# 21_Peripherals.net
KiCad netlist of a schematic drawn in Altium Designer
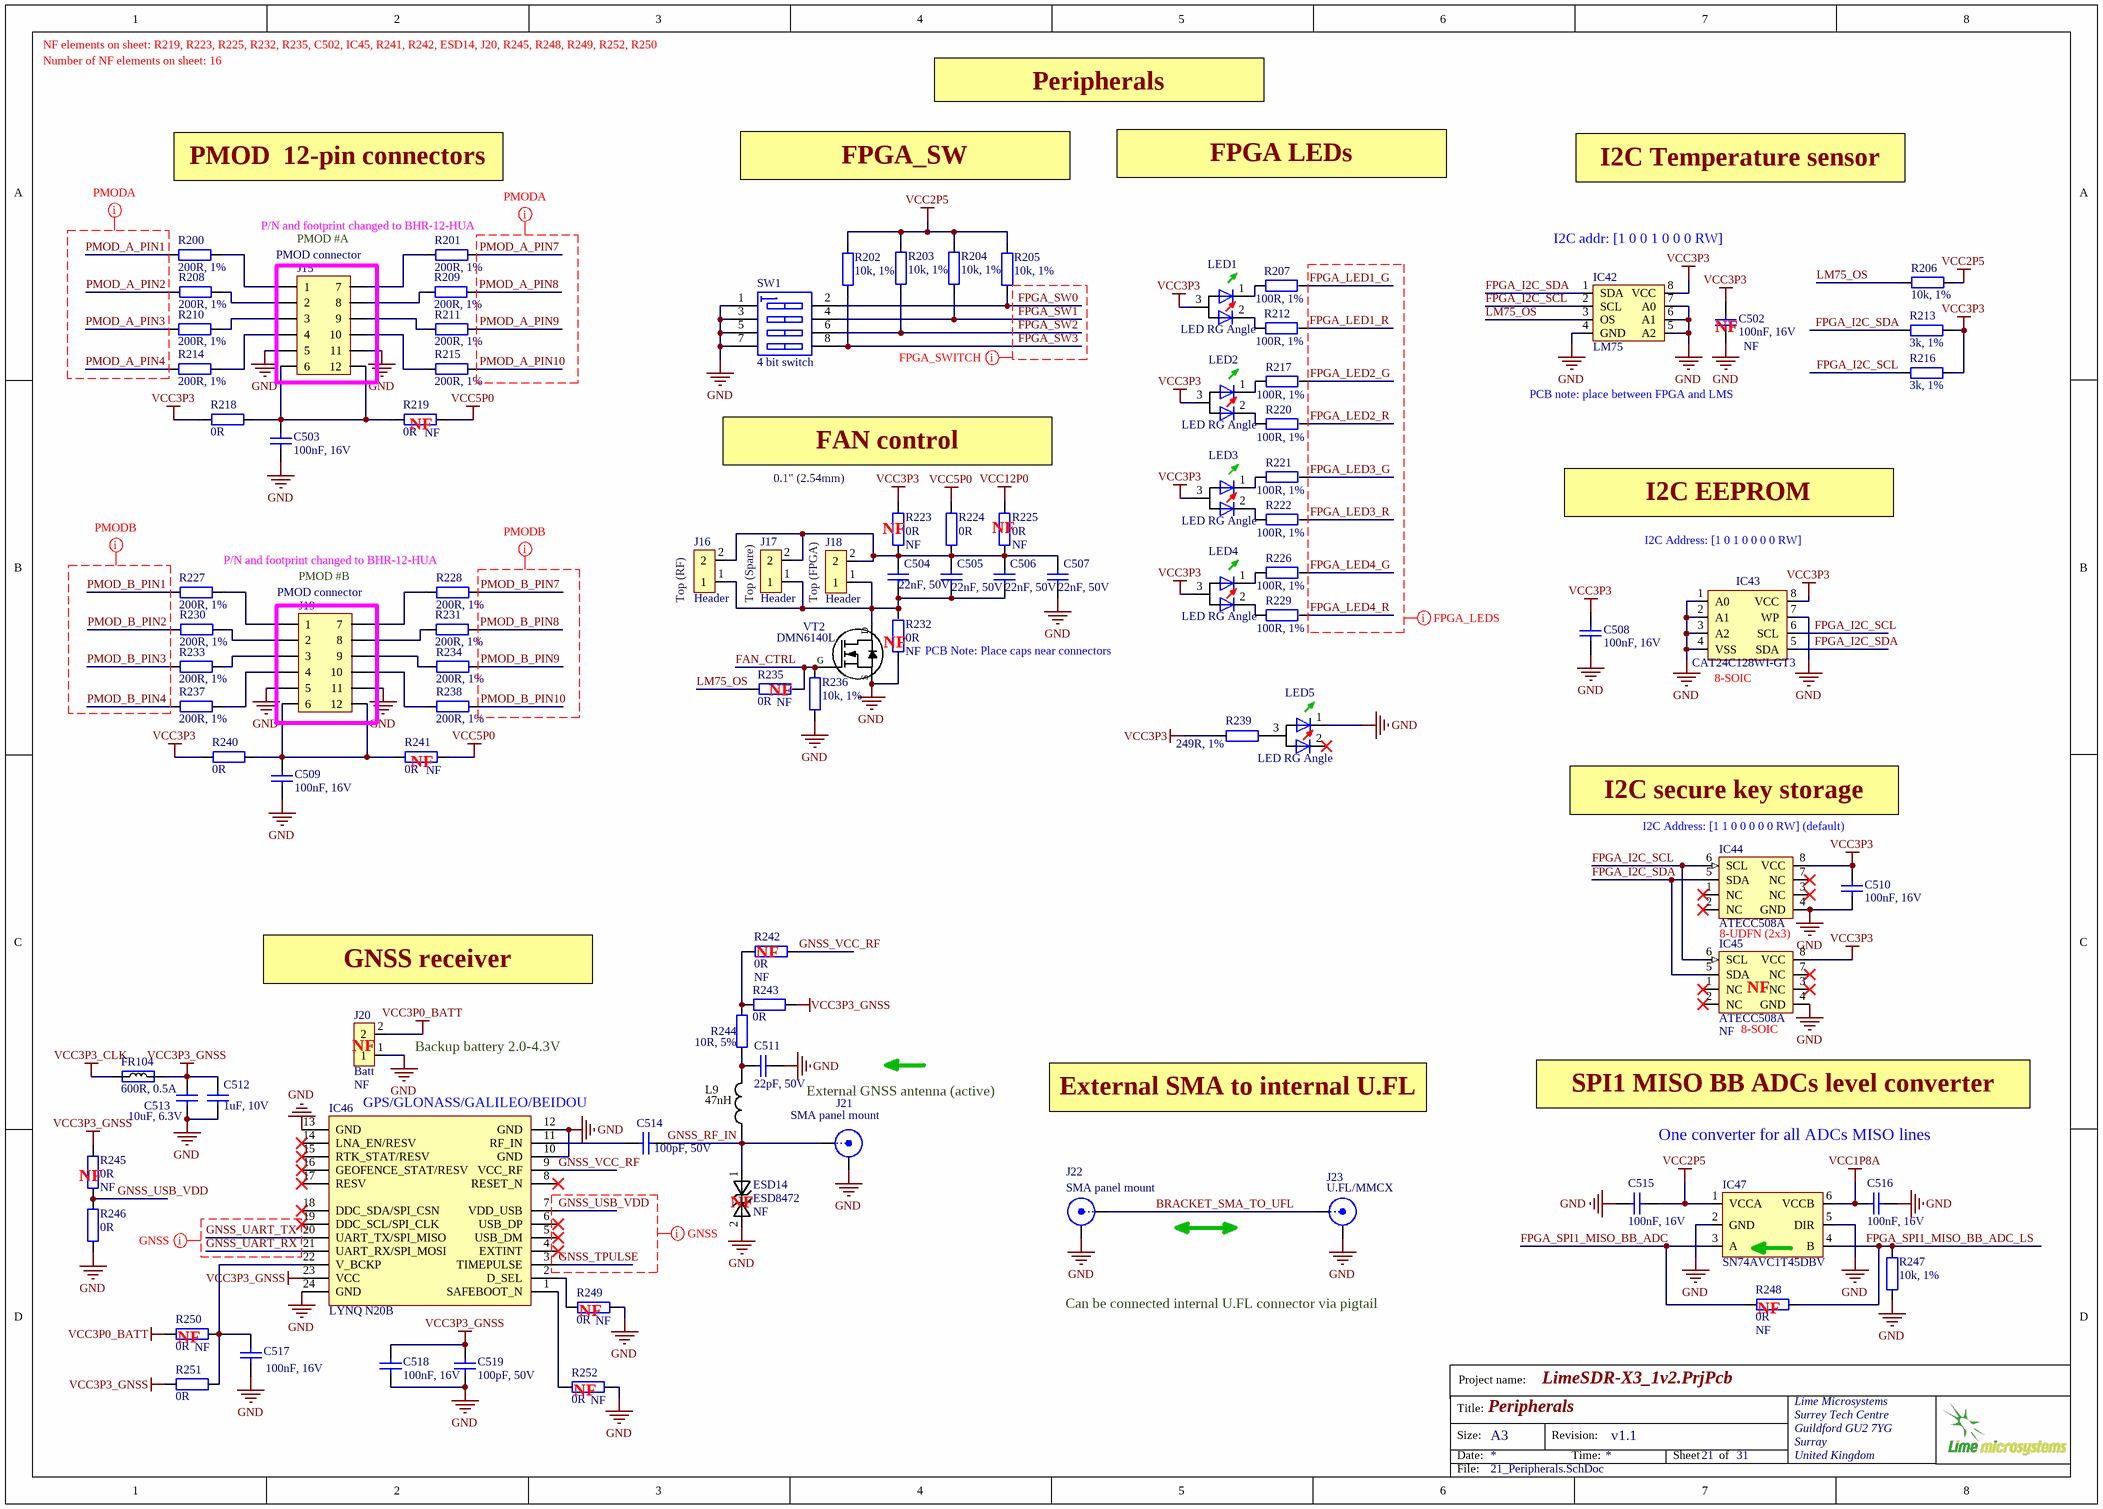
[diagram p0: 21_Peripherals.SchDoc]

(export (version "E")
  (design (tool "Eeschema 10.0.6"))
  (components
    (comp (ref "C502")
      (value "100nF, 16V")
      (footprint "CAP0402")
      (fields
        (field (name "TOLERANCE") "10 %")
        (field (name "MANUFACTURER") "Murata Electronics")
        (field (name "ASSEMBLY INFO") "NF")
      )
      (libsource (lib "") (part "Cap_0603_3"))
    )
    (comp (ref "C503")
      (value "100nF, 16V")
      (footprint "CAP0402")
      (fields
        (field (name "TOLERANCE") "10 %")
        (field (name "MANUFACTURER") "Murata Electronics")
        (field (name "MANUFACTURER PART NUMBER") "GRM155R71C104KA88D")
      )
      (libsource (lib "") (part "Cap_0603_1"))
    )
    (comp (ref "C504")
      (value "22nF, 50V")
      (footprint "CAP0402")
      (fields (field (name "TOLERANCE") "±10%") (field (name "MANUFACTURER") "Kemet"))
      (libsource (lib "") (part "Cap_0402_2"))
    )
    (comp (ref "C505")
      (value "22nF, 50V")
      (footprint "CAP0402")
      (fields (field (name "TOLERANCE") "±10%") (field (name "MANUFACTURER") "Kemet"))
      (libsource (lib "") (part "Cap_0402_1"))
    )
    (comp (ref "C506")
      (value "22nF, 50V")
      (footprint "CAP0402")
      (fields (field (name "TOLERANCE") "±10%") (field (name "MANUFACTURER") "Kemet"))
      (libsource (lib "") (part "Cap_0402_1"))
    )
    (comp (ref "C507")
      (value "22nF, 50V")
      (footprint "CAP0402")
      (fields (field (name "TOLERANCE") "±10%") (field (name "MANUFACTURER") "Kemet"))
      (libsource (lib "") (part "Cap_0402_1"))
    )
    (comp (ref "C508")
      (value "100nF, 16V")
      (footprint "CAP0402")
      (fields (field (name "TOLERANCE") "10 %") (field (name "MANUFACTURER") "Murata Electronics"))
      (libsource (lib "") (part "Cap_0603_2"))
    )
    (comp (ref "C509")
      (value "100nF, 16V")
      (footprint "CAP0402")
      (fields
        (field (name "TOLERANCE") "10 %")
        (field (name "MANUFACTURER") "Murata Electronics")
        (field (name "MANUFACTURER PART NUMBER") "GRM155R71C104KA88D")
      )
      (libsource (lib "") (part "Cap_0603_1"))
    )
    (comp (ref "C510")
      (value "100nF, 16V")
      (footprint "CAP0402")
      (fields (field (name "TOLERANCE") "10 %") (field (name "MANUFACTURER") "Murata Electronics"))
      (libsource (lib "") (part "Cap_0603_2"))
    )
    (comp (ref "C511")
      (value "22pF, 50V")
      (footprint "CAP0402")
      (fields (field (name "TOLERANCE") "±5%") (field (name "MANUFACTURER") "Yageo"))
      (libsource (lib "LimeMicroAltiumLib_schLib") (part "Cap_0402"))
    )
    (comp (ref "C512")
      (value "1uF, 10V")
      (footprint "CAP0402")
      (description "CAP CER 1UF 10V X5R 0402")
      (fields (field (name "MANUFACTURER") "TDK"))
      (libsource (lib "LimeMicroAltiumLib_schLib") (part "Cap_0402"))
    )
    (comp (ref "C513")
      (value "10uF, 6.3V")
      (footprint "CAP0603")
      (fields (field (name "TOLERANCE") "±20%") (field (name "MANUFACTURER") "Yageo"))
      (libsource (lib "") (part "Cap_0603_1"))
    )
    (comp (ref "C514")
      (value "100pF, 50V")
      (footprint "CAP0402")
      (fields (field (name "TOLERANCE") "±5%") (field (name "MANUFACTURER") "Yageo"))
      (libsource (lib "LimeMicroAltiumLib_schLib") (part "Cap_0402"))
    )
    (comp (ref "C515")
      (value "100nF, 16V")
      (footprint "CAP0402")
      (fields (field (name "TOLERANCE") "10 %") (field (name "MANUFACTURER") "Murata Electronics"))
      (libsource (lib "LimeFPGAboard_schLib") (part "Cap_0603"))
    )
    (comp (ref "C516")
      (value "100nF, 16V")
      (footprint "CAP0402")
      (fields (field (name "TOLERANCE") "10 %") (field (name "MANUFACTURER") "Murata Electronics"))
      (libsource (lib "LimeFPGAboard_schLib") (part "Cap_0603"))
    )
    (comp (ref "C517")
      (value "100nF, 16V")
      (footprint "CAP0402")
      (fields
        (field (name "TOLERANCE") "10 %")
        (field (name "MANUFACTURER") "Murata Electronics")
        (field (name "MANUFACTURER PART NUMBER") "GRM155R71C104KA88D")
      )
      (libsource (lib "") (part "Cap_0603_1"))
    )
    (comp (ref "C518")
      (value "100nF, 16V")
      (footprint "CAP0402")
      (fields
        (field (name "MANUFACTURER") "Murata Electronics")
        (field (name "TOLERANCE") "10 %")
        (field (name "MANUFACTURER PART NUMBER") "GRM155R71C104KA88D")
      )
      (libsource (lib "LimeMicroAltiumLib_schLib") (part "Cap_0402"))
    )
    (comp (ref "C519")
      (value "100pF, 50V")
      (footprint "CAP0402")
      (fields (field (name "TOLERANCE") "±5%") (field (name "MANUFACTURER") "Yageo"))
      (libsource (lib "LimeMicroAltiumLib_schLib") (part "Cap_0402"))
    )
    (comp (ref "ESD14")
      (value "ESD8472")
      (footprint "ESD8472_X3DFN2")
      (fields
        (field (name "MANUFACTURER") "ON Semiconductor")
        (field (name "MANUFACTURER PART NUMBER") "ESD8472MUT5G")
        (field (name "ASSEMBLY INFO") "NF")
      )
      (libsource (lib "LimeMicroAltiumLib_schLib") (part "ESD8472"))
    )
    (comp (ref "FR104")
      (value "600R, 0.5A")
      (footprint "RES0402")
      (fields
        (field (name "MANUFACTURER") "Murata")
        (field (name "TOLERANCE") "25%")
        (field (name "Comment") "Ferrite")
      )
      (libsource (lib "LimeMicroAltiumLib_schLib") (part "Ferrite"))
    )
    (comp (ref "IC42")
      (value "LM75")
      (footprint "HWSON8_LM75")
      (fields (field (name "MANUFACTURER") "NXP Semiconductors"))
      (libsource (lib "LimeMicroAltiumLib_schLib") (part "LM75"))
    )
    (comp (ref "IC43")
      (value "CAT24C128WI-GT3")
      (footprint "SOIC127P600-8DL_v2")
      (fields (field (name "MANUFACTURER") "ON Semiconductor") (field (name "BASE PART NUMBER") "CAT24C128"))
      (libsource (lib "LimeMicroAltiumLib_schLib") (part "24FC64F"))
    )
    (comp (ref "IC44")
      (value "ATECC508A")
      (footprint "ATECC508A_UDFN8")
      (fields (field (name "MANUFACTURER") "Microchip"))
      (libsource (lib "") (part "ATECC508A_authentication_IC_1"))
    )
    (comp (ref "IC45")
      (value "ATECC508A")
      (footprint "SOIC127P600-8DL_v2")
      (fields
        (field (name "ASSEMBLY INFO") "NF")
        (field (name "MANUFACTURER") "Microchip Technology")
        (field (name "BASE PART NUMBER") "ATECC508")
      )
      (libsource (lib "LimeMicroAltiumLib_schLib_r01") (part "ATECC508A_authentication_IC"))
    )
    (comp (ref "IC46")
      (value "LYNQ N20B")
      (footprint "NEO-7M/8M")
      (description "GNSS engine for GPS/QZSS, GLONASS")
      (fields (field (name "MANUFACTURER") "RF channe;"))
      (libsource (lib "LimeMicroAltiumLib_schLib") (part "NEO-M8P_M8M"))
    )
    (comp (ref "IC47")
      (value "SN74AVC1T45DBV")
      (footprint "SOT23-6")
      (fields (field (name "MANUFACTURER") "Texas Instruments"))
      (libsource (lib "LimeMicroAltiumLib_schLib_r01") (part "SN74AVC1T45DBV"))
    )
    (comp (ref "J15")
      (value "PMOD connector")
      (footprint "HEADER6X_TH_RIGHT_ANGLE_LOCK")
      (description "Header, 4-Pin, Dual row")
      (fields (field (name "MANUFACTURER") "Adam Equipment"))
      (libsource (lib "LimeMicroAltiumLib_schLib") (part "PMOD_connector"))
    )
    (comp (ref "J16")
      (value "Header")
      (footprint "HDR_1x2")
      (fields (field (name "MANUFACTURER") "Wurth Electronics"))
      (libsource (lib "LimeFPGAboard_schLib") (part "Jumper"))
    )
    (comp (ref "J17")
      (value "Header")
      (footprint "HDR_1x2")
      (fields (field (name "MANUFACTURER") "Wurth Electronics"))
      (libsource (lib "LimeFPGAboard_schLib") (part "Jumper"))
    )
    (comp (ref "J18")
      (value "Header")
      (footprint "HDR_1x2")
      (fields (field (name "MANUFACTURER") "Wurth Electronics"))
      (libsource (lib "LimeFPGAboard_schLib") (part "Jumper"))
    )
    (comp (ref "J19")
      (value "PMOD connector")
      (footprint "HEADER6X_TH_RIGHT_ANGLE_LOCK")
      (description "Header, 4-Pin, Dual row")
      (fields (field (name "MANUFACTURER") "Adam Equipment"))
      (libsource (lib "LimeMicroAltiumLib_schLib") (part "PMOD_connector"))
    )
    (comp (ref "J20")
      (value "Batt")
      (footprint "HDR_1x2")
      (fields (field (name "ASSEMBLY INFO") "NF") (field (name "MANUFACTURER") "3M"))
      (libsource (lib "") (part "Jumper_1"))
    )
    (comp (ref "J21")
      (value "SMA panel mount")
      (footprint "SMA_connector_side")
      (description "CONN SMA JACK STR 50OHM EDGE MNT")
      (fields (field (name "MANUFACTURER") "Linx"))
      (libsource (lib "") (part "RF_IF_connector_1"))
    )
    (comp (ref "J22")
      (value "SMA panel mount")
      (footprint "SMA_connector_side")
      (description "CONN SMA JACK STR 50OHM EDGE MNT")
      (fields (field (name "MANUFACTURER") "Linx"))
      (libsource (lib "") (part "RF_IF_connector_1"))
    )
    (comp (ref "J23")
      (value "U.FL/MMCX")
      (footprint "MMCX_UFL_conn_u")
      (description "CONN UMC RCPT STR 50 OHM SMD")
      (fields (field (name "MANUFACTURER") "Molex, LLC"))
      (libsource (lib "LimeMicroAltiumLib_schLib") (part "RF_IF_connector"))
    )
    (comp (ref "L9")
      (value "47nH")
      (footprint "RES0402")
      (fields
        (field (name "MANUFACTURER") "COILCRAFT")
        (field (name "MANUFACTURER PART NUMBER") "0402HP-47NXJLU")
      )
      (libsource (lib "LimeMicroAltiumLib_schLib") (part "Inductor_0603"))
    )
    (comp (ref "LED1")
      (value "LED RG Angle")
      (footprint "LED_RG_RIGHT_ANGLE_v3")
      (fields (field (name "MANUFACTURER") "Stanley Electric"))
      (libsource (lib "LimeMicroAltiumLib_schLib_r03") (part "LED_green_red_right_angle_v2"))
    )
    (comp (ref "LED2")
      (value "LED RG Angle")
      (footprint "LED_RG_RIGHT_ANGLE_v3")
      (fields (field (name "MANUFACTURER") "Stanley Electric"))
      (libsource (lib "LimeMicroAltiumLib_schLib_r03") (part "LED_green_red_right_angle_v2"))
    )
    (comp (ref "LED3")
      (value "LED RG Angle")
      (footprint "LED_RG_RIGHT_ANGLE_v3")
      (fields (field (name "MANUFACTURER") "Stanley Electric"))
      (libsource (lib "LimeMicroAltiumLib_schLib_r03") (part "LED_green_red_right_angle_v2"))
    )
    (comp (ref "LED4")
      (value "LED RG Angle")
      (footprint "LED_RG_RIGHT_ANGLE_v3")
      (fields (field (name "MANUFACTURER") "Stanley Electric"))
      (libsource (lib "LimeMicroAltiumLib_schLib_r03") (part "LED_green_red_right_angle_v2"))
    )
    (comp (ref "LED5")
      (value "LED RG Angle")
      (footprint "LED_RG_RIGHT_ANGLE_v3")
      (fields (field (name "MANUFACTURER") "Stanley Electric"))
      (libsource (lib "LimeMicroAltiumLib_schLib_r03") (part "LED_green_red_right_angle_v2"))
    )
    (comp (ref "R200")
      (value "200R, 1%")
      (footprint "RES0402")
      (fields (field (name "MANUFACTURER") "Yageo") (field (name "TOLERANCE") "1%"))
      (libsource (lib "LimeMicroAltiumLib_schLib") (part "Res_0402"))
    )
    (comp (ref "R201")
      (value "200R, 1%")
      (footprint "RES0402")
      (fields (field (name "MANUFACTURER") "Yageo") (field (name "TOLERANCE") "1%"))
      (libsource (lib "LimeMicroAltiumLib_schLib") (part "Res_0402"))
    )
    (comp (ref "R202")
      (value "10k, 1%")
      (footprint "RES0402")
      (fields (field (name "MANUFACTURER") "Yageo") (field (name "TOLERANCE") "±1%"))
      (libsource (lib "LimeMicroAltiumLib_schLib") (part "Res_0402"))
    )
    (comp (ref "R203")
      (value "10k, 1%")
      (footprint "RES0402")
      (fields (field (name "MANUFACTURER") "Yageo") (field (name "TOLERANCE") "±1%"))
      (libsource (lib "LimeMicroAltiumLib_schLib") (part "Res_0402"))
    )
    (comp (ref "R204")
      (value "10k, 1%")
      (footprint "RES0402")
      (fields (field (name "MANUFACTURER") "Yageo") (field (name "TOLERANCE") "±1%"))
      (libsource (lib "LimeMicroAltiumLib_schLib") (part "Res_0402"))
    )
    (comp (ref "R205")
      (value "10k, 1%")
      (footprint "RES0402")
      (fields (field (name "MANUFACTURER") "Yageo") (field (name "TOLERANCE") "±1%"))
      (libsource (lib "LimeMicroAltiumLib_schLib") (part "Res_0402"))
    )
    (comp (ref "R206")
      (value "10k, 1%")
      (footprint "RES0402")
      (fields (field (name "MANUFACTURER") "Yageo") (field (name "TOLERANCE") "±1%"))
      (libsource (lib "") (part "Res_0402_1"))
    )
    (comp (ref "R207")
      (value "100R, 1%")
      (footprint "RES0402")
      (fields (field (name "TOLERANCE") "±1%") (field (name "MANUFACTURER") "Stackpole Electronics Inc."))
      (libsource (lib "") (part "Res_0402_1"))
    )
    (comp (ref "R208")
      (value "200R, 1%")
      (footprint "RES0402")
      (fields (field (name "MANUFACTURER") "Yageo") (field (name "TOLERANCE") "1%"))
      (libsource (lib "LimeMicroAltiumLib_schLib") (part "Res_0402"))
    )
    (comp (ref "R209")
      (value "200R, 1%")
      (footprint "RES0402")
      (fields (field (name "MANUFACTURER") "Yageo") (field (name "TOLERANCE") "1%"))
      (libsource (lib "LimeMicroAltiumLib_schLib") (part "Res_0402"))
    )
    (comp (ref "R210")
      (value "200R, 1%")
      (footprint "RES0402")
      (fields (field (name "MANUFACTURER") "Yageo") (field (name "TOLERANCE") "1%"))
      (libsource (lib "LimeMicroAltiumLib_schLib") (part "Res_0402"))
    )
    (comp (ref "R211")
      (value "200R, 1%")
      (footprint "RES0402")
      (fields (field (name "MANUFACTURER") "Yageo") (field (name "TOLERANCE") "1%"))
      (libsource (lib "LimeMicroAltiumLib_schLib") (part "Res_0402"))
    )
    (comp (ref "R212")
      (value "100R, 1%")
      (footprint "RES0402")
      (fields (field (name "TOLERANCE") "±1%") (field (name "MANUFACTURER") "Stackpole Electronics Inc."))
      (libsource (lib "") (part "Res_0402_1"))
    )
    (comp (ref "R213")
      (value "3k, 1%")
      (footprint "RES0402")
      (fields (field (name "TOLERANCE") "±1%") (field (name "MANUFACTURER") "Vishay Dale"))
      (libsource (lib "") (part "Res_0402_1"))
    )
    (comp (ref "R214")
      (value "200R, 1%")
      (footprint "RES0402")
      (fields (field (name "MANUFACTURER") "Yageo") (field (name "TOLERANCE") "1%"))
      (libsource (lib "LimeMicroAltiumLib_schLib") (part "Res_0402"))
    )
    (comp (ref "R215")
      (value "200R, 1%")
      (footprint "RES0402")
      (fields (field (name "MANUFACTURER") "Yageo") (field (name "TOLERANCE") "1%"))
      (libsource (lib "LimeMicroAltiumLib_schLib") (part "Res_0402"))
    )
    (comp (ref "R216")
      (value "3k, 1%")
      (footprint "RES0402")
      (fields (field (name "TOLERANCE") "±1%") (field (name "MANUFACTURER") "Vishay Dale"))
      (libsource (lib "") (part "Res_0402_1"))
    )
    (comp (ref "R217")
      (value "100R, 1%")
      (footprint "RES0402")
      (fields (field (name "TOLERANCE") "±1%") (field (name "MANUFACTURER") "Stackpole Electronics Inc."))
      (libsource (lib "") (part "Res_0402_1"))
    )
    (comp (ref "R218")
      (value "0R")
      (footprint "RES0402")
      (fields (field (name "MANUFACTURER") "Yageo"))
      (libsource (lib "LimeFPGAboard_schLib") (part "Res_0402"))
    )
    (comp (ref "R219")
      (value "0R")
      (footprint "RES0402")
      (fields (field (name "MANUFACTURER") "Yageo") (field (name "ASSEMBLY INFO") "NF"))
      (libsource (lib "LimeFPGAboard_schLib") (part "Res_0402"))
    )
    (comp (ref "R220")
      (value "100R, 1%")
      (footprint "RES0402")
      (fields (field (name "TOLERANCE") "±1%") (field (name "MANUFACTURER") "Stackpole Electronics Inc."))
      (libsource (lib "") (part "Res_0402_1"))
    )
    (comp (ref "R221")
      (value "100R, 1%")
      (footprint "RES0402")
      (fields (field (name "TOLERANCE") "±1%") (field (name "MANUFACTURER") "Stackpole Electronics Inc."))
      (libsource (lib "") (part "Res_0402_1"))
    )
    (comp (ref "R222")
      (value "100R, 1%")
      (footprint "RES0402")
      (fields (field (name "TOLERANCE") "±1%") (field (name "MANUFACTURER") "Stackpole Electronics Inc."))
      (libsource (lib "") (part "Res_0402_1"))
    )
    (comp (ref "R223")
      (value "0R")
      (footprint "RES0402")
      (fields
        (field (name "ASSEMBLY INFO") "NF")
        (field (name "MANUFACTURER") "Yageo")
        (field (name "TOLERANCE") "Jumper")
      )
      (libsource (lib "") (part "Res_0402_1"))
    )
    (comp (ref "R224")
      (value "0R")
      (footprint "RES0402")
      (fields (field (name "MANUFACTURER") "Yageo") (field (name "TOLERANCE") "Jumper"))
      (libsource (lib "") (part "Res_0402_1"))
    )
    (comp (ref "R225")
      (value "0R")
      (footprint "RES0402")
      (fields
        (field (name "ASSEMBLY INFO") "NF")
        (field (name "MANUFACTURER") "Yageo")
        (field (name "TOLERANCE") "Jumper")
      )
      (libsource (lib "") (part "Res_0402_1"))
    )
    (comp (ref "R226")
      (value "100R, 1%")
      (footprint "RES0402")
      (fields (field (name "TOLERANCE") "±1%") (field (name "MANUFACTURER") "Stackpole Electronics Inc."))
      (libsource (lib "") (part "Res_0402_1"))
    )
    (comp (ref "R227")
      (value "200R, 1%")
      (footprint "RES0402")
      (fields (field (name "MANUFACTURER") "Yageo") (field (name "TOLERANCE") "1%"))
      (libsource (lib "LimeMicroAltiumLib_schLib") (part "Res_0402"))
    )
    (comp (ref "R228")
      (value "200R, 1%")
      (footprint "RES0402")
      (fields (field (name "MANUFACTURER") "Yageo") (field (name "TOLERANCE") "1%"))
      (libsource (lib "LimeMicroAltiumLib_schLib") (part "Res_0402"))
    )
    (comp (ref "R229")
      (value "100R, 1%")
      (footprint "RES0402")
      (fields (field (name "TOLERANCE") "±1%") (field (name "MANUFACTURER") "Stackpole Electronics Inc."))
      (libsource (lib "") (part "Res_0402_1"))
    )
    (comp (ref "R230")
      (value "200R, 1%")
      (footprint "RES0402")
      (fields (field (name "MANUFACTURER") "Yageo") (field (name "TOLERANCE") "1%"))
      (libsource (lib "LimeMicroAltiumLib_schLib") (part "Res_0402"))
    )
    (comp (ref "R231")
      (value "200R, 1%")
      (footprint "RES0402")
      (fields (field (name "MANUFACTURER") "Yageo") (field (name "TOLERANCE") "1%"))
      (libsource (lib "LimeMicroAltiumLib_schLib") (part "Res_0402"))
    )
    (comp (ref "R232")
      (value "0R")
      (footprint "RES0402")
      (fields
        (field (name "ASSEMBLY INFO") "NF")
        (field (name "MANUFACTURER") "Yageo")
        (field (name "TOLERANCE") "Jumper")
      )
      (libsource (lib "") (part "Res_0402_1"))
    )
    (comp (ref "R233")
      (value "200R, 1%")
      (footprint "RES0402")
      (fields (field (name "MANUFACTURER") "Yageo") (field (name "TOLERANCE") "1%"))
      (libsource (lib "LimeMicroAltiumLib_schLib") (part "Res_0402"))
    )
    (comp (ref "R234")
      (value "200R, 1%")
      (footprint "RES0402")
      (fields (field (name "MANUFACTURER") "Yageo") (field (name "TOLERANCE") "1%"))
      (libsource (lib "LimeMicroAltiumLib_schLib") (part "Res_0402"))
    )
    (comp (ref "R235")
      (value "0R")
      (footprint "RES0402")
      (fields (field (name "MANUFACTURER") "Yageo") (field (name "ASSEMBLY INFO") "NF"))
      (libsource (lib "") (part "Res_0402_1"))
    )
    (comp (ref "R236")
      (value "10k, 1%")
      (footprint "RES0402")
      (fields (field (name "MANUFACTURER") "Yageo") (field (name "TOLERANCE") "±1%"))
      (libsource (lib "") (part "Res_0402_1"))
    )
    (comp (ref "R237")
      (value "200R, 1%")
      (footprint "RES0402")
      (fields (field (name "MANUFACTURER") "Yageo") (field (name "TOLERANCE") "1%"))
      (libsource (lib "LimeMicroAltiumLib_schLib") (part "Res_0402"))
    )
    (comp (ref "R238")
      (value "200R, 1%")
      (footprint "RES0402")
      (fields (field (name "MANUFACTURER") "Yageo") (field (name "TOLERANCE") "1%"))
      (libsource (lib "LimeMicroAltiumLib_schLib") (part "Res_0402"))
    )
    (comp (ref "R239")
      (value "249R, 1%")
      (footprint "RES0402")
      (fields (field (name "MANUFACTURER") "Stackpole Electronics Inc") (field (name "TOLERANCE") "±1%"))
      (libsource (lib "") (part "Res_0402_1"))
    )
    (comp (ref "R240")
      (value "0R")
      (footprint "RES0402")
      (fields (field (name "MANUFACTURER") "Yageo"))
      (libsource (lib "LimeFPGAboard_schLib") (part "Res_0402"))
    )
    (comp (ref "R241")
      (value "0R")
      (footprint "RES0402")
      (fields (field (name "MANUFACTURER") "Yageo") (field (name "ASSEMBLY INFO") "NF"))
      (libsource (lib "LimeFPGAboard_schLib") (part "Res_0402"))
    )
    (comp (ref "R242")
      (value "0R")
      (footprint "RES0402")
      (fields
        (field (name "ASSEMBLY INFO") "NF")
        (field (name "MANUFACTURER") "Yageo")
        (field (name "TOLERANCE") "Jumper")
      )
      (libsource (lib "LimeMicroAltiumLib_schLib") (part "Res_0402"))
    )
    (comp (ref "R243")
      (value "0R")
      (footprint "RES0402")
      (fields (field (name "MANUFACTURER") "Yageo") (field (name "TOLERANCE") "Jumper"))
      (libsource (lib "LimeMicroAltiumLib_schLib") (part "Res_0402"))
    )
    (comp (ref "R244")
      (value "10R, 5%")
      (footprint "RES0402")
      (fields (field (name "TOLERANCE") "±5%") (field (name "MANUFACTURER") "Yageo"))
      (libsource (lib "LimeMicroAltiumLib_schLib") (part "Res_0402"))
    )
    (comp (ref "R245")
      (value "0R")
      (footprint "RES0402")
      (fields
        (field (name "ASSEMBLY INFO") "NF")
        (field (name "MANUFACTURER") "Yageo")
        (field (name "TOLERANCE") "Jumper")
      )
      (libsource (lib "LimeMicroAltiumLib_schLib") (part "Res_0402"))
    )
    (comp (ref "R246")
      (value "0R")
      (footprint "RES0402")
      (fields (field (name "MANUFACTURER") "Yageo") (field (name "TOLERANCE") "Jumper"))
      (libsource (lib "LimeMicroAltiumLib_schLib") (part "Res_0402"))
    )
    (comp (ref "R247")
      (value "10k, 1%")
      (footprint "RES0402")
      (fields (field (name "MANUFACTURER") "Yageo") (field (name "TOLERANCE") "±1%"))
      (libsource (lib "") (part "Res_0402_1"))
    )
    (comp (ref "R248")
      (value "0R")
      (footprint "RES0402")
      (fields
        (field (name "ASSEMBLY INFO") "NF")
        (field (name "MANUFACTURER") "Yageo")
        (field (name "TOLERANCE") "Jumper")
      )
      (libsource (lib "") (part "Res_0402_1"))
    )
    (comp (ref "R249")
      (value "0R")
      (footprint "RES0402")
      (fields
        (field (name "ASSEMBLY INFO") "NF")
        (field (name "MANUFACTURER") "Yageo")
        (field (name "TOLERANCE") "Jumper")
      )
      (libsource (lib "LimeMicroAltiumLib_schLib") (part "Res_0402"))
    )
    (comp (ref "R250")
      (value "0R")
      (footprint "RES0402")
      (fields
        (field (name "ASSEMBLY INFO") "NF")
        (field (name "MANUFACTURER") "Yageo")
        (field (name "TOLERANCE") "Jumper")
      )
      (libsource (lib "LimeMicroAltiumLib_schLib") (part "Res_0402"))
    )
    (comp (ref "R251")
      (value "0R")
      (footprint "RES0402")
      (fields (field (name "MANUFACTURER") "Yageo") (field (name "TOLERANCE") "Jumper"))
      (libsource (lib "LimeMicroAltiumLib_schLib") (part "Res_0402"))
    )
    (comp (ref "R252")
      (value "0R")
      (footprint "RES0402")
      (fields
        (field (name "ASSEMBLY INFO") "NF")
        (field (name "MANUFACTURER") "Yageo")
        (field (name "TOLERANCE") "Jumper")
      )
      (libsource (lib "LimeMicroAltiumLib_schLib") (part "Res_0402"))
    )
    (comp (ref "SW1")
      (value "4 bit switch")
      (footprint "DS02C-254-1L-04BE_DIP_SWITCH_4PIN")
      (fields (field (name "MANUFACTURER") "CUI Devices"))
      (libsource (lib "LimeMicroAltiumLib_schLib_r03") (part "SW_SM_4bit_v2"))
    )
    (comp (ref "VT2")
      (value "DMN6140L")
      (footprint "SOT23-3")
      (description "NDS331N")
      (fields
        (field (name "MANUFACTURER PART NUMBER") "DMN6140L-13")
        (field (name "MANUFACTURER") "Diodes Incorporated")
      )
      (libsource (lib "LimeFPGAboard_schLib") (part "NDS331N"))
    )
  )
  (nets
    (net (code "1") (name "/BRACKET_SMA_TO_UFL") (class "Default")
      (node (ref "J22") (pin "1") (pinfunction "X_1") (pintype "passive"))
      (node (ref "J23") (pin "1") (pinfunction "X_1") (pintype "passive"))
    )
    (net (code "2") (name "/FAN_CTRL") (class "Default")
      (node (ref "R235") (pin "2") (pinfunction "2_2") (pintype "passive"))
      (node (ref "R236") (pin "1") (pinfunction "1_1") (pintype "passive"))
      (node (ref "VT2") (pin "G") (pinfunction "G_G") (pintype "passive"))
    )
    (net (code "3") (name "/FPGA_I2C_SCL") (class "Default")
      (node (ref "IC42") (pin "2") (pinfunction "SCL_2") (pintype "passive"))
      (node (ref "IC43") (pin "6") (pinfunction "SCL_6") (pintype "passive"))
      (node (ref "IC44") (pin "6") (pinfunction "SCL_6") (pintype "input"))
      (node (ref "IC45") (pin "6") (pinfunction "SCL_6") (pintype "input"))
      (node (ref "R216") (pin "2") (pinfunction "2_2") (pintype "passive"))
    )
    (net (code "4") (name "/FPGA_I2C_SDA") (class "Default")
      (node (ref "IC42") (pin "1") (pinfunction "SDA_1") (pintype "passive"))
      (node (ref "IC43") (pin "5") (pinfunction "SDA_5") (pintype "passive"))
      (node (ref "IC44") (pin "5") (pinfunction "SDA_5") (pintype "bidirectional"))
      (node (ref "IC45") (pin "5") (pinfunction "SDA_5") (pintype "bidirectional"))
      (node (ref "R213") (pin "2") (pinfunction "2_2") (pintype "passive"))
    )
    (net (code "5") (name "/FPGA_LED1_G") (class "Default")
      (node (ref "R207") (pin "2") (pinfunction "2_2") (pintype "passive"))
    )
    (net (code "6") (name "/FPGA_LED1_R") (class "Default")
      (node (ref "R212") (pin "2") (pinfunction "2_2") (pintype "passive"))
    )
    (net (code "7") (name "/FPGA_LED2_G") (class "Default")
      (node (ref "R217") (pin "2") (pinfunction "2_2") (pintype "passive"))
    )
    (net (code "8") (name "/FPGA_LED2_R") (class "Default")
      (node (ref "R220") (pin "2") (pinfunction "2_2") (pintype "passive"))
    )
    (net (code "9") (name "/FPGA_LED3_G") (class "Default")
      (node (ref "R221") (pin "2") (pinfunction "2_2") (pintype "passive"))
    )
    (net (code "10") (name "/FPGA_LED3_R") (class "Default")
      (node (ref "R222") (pin "2") (pinfunction "2_2") (pintype "passive"))
    )
    (net (code "11") (name "/FPGA_LED4_G") (class "Default")
      (node (ref "R226") (pin "2") (pinfunction "2_2") (pintype "passive"))
    )
    (net (code "12") (name "/FPGA_LED4_R") (class "Default")
      (node (ref "R229") (pin "2") (pinfunction "2_2") (pintype "passive"))
    )
    (net (code "13") (name "/FPGA_SPI1_MISO_BB_ADC") (class "Default")
      (node (ref "IC47") (pin "3") (pinfunction "A_3") (pintype "bidirectional"))
      (node (ref "R248") (pin "2") (pinfunction "2_2") (pintype "passive"))
    )
    (net (code "14") (name "/FPGA_SPI1_MISO_BB_ADC_LS") (class "Default")
      (node (ref "IC47") (pin "4") (pinfunction "B_4") (pintype "bidirectional"))
      (node (ref "R247") (pin "2") (pinfunction "2_2") (pintype "passive"))
      (node (ref "R248") (pin "1") (pinfunction "1_1") (pintype "passive"))
    )
    (net (code "15") (name "/FPGA_SW0") (class "Default")
      (node (ref "R205") (pin "2") (pinfunction "2_2") (pintype "passive"))
      (node (ref "SW1") (pin "2") (pinfunction "B1_2") (pintype "passive"))
    )
    (net (code "16") (name "/FPGA_SW1") (class "Default")
      (node (ref "R204") (pin "2") (pinfunction "2_2") (pintype "passive"))
      (node (ref "SW1") (pin "4") (pinfunction "B2_4") (pintype "passive"))
    )
    (net (code "17") (name "/FPGA_SW2") (class "Default")
      (node (ref "R203") (pin "2") (pinfunction "2_2") (pintype "passive"))
      (node (ref "SW1") (pin "6") (pinfunction "B3_6") (pintype "passive"))
    )
    (net (code "18") (name "/FPGA_SW3") (class "Default")
      (node (ref "R202") (pin "2") (pinfunction "2_2") (pintype "passive"))
      (node (ref "SW1") (pin "8") (pinfunction "B4_8") (pintype "passive"))
    )
    (net (code "19") (name "/GNSS_RF_IN") (class "Default")
      (node (ref "C514") (pin "1") (pinfunction "1_1") (pintype "passive"))
      (node (ref "ESD14") (pin "1") (pinfunction "1_1") (pintype "passive"))
      (node (ref "J21") (pin "1") (pinfunction "X_1") (pintype "passive"))
      (node (ref "L9") (pin "1") (pinfunction "1_1") (pintype "passive"))
    )
    (net (code "20") (name "/GNSS_TPULSE") (class "Default")
      (node (ref "IC46") (pin "3") (pinfunction "TIMEPULSE_3") (pintype "passive"))
    )
    (net (code "21") (name "/GNSS_UART_RX") (class "Default")
      (node (ref "IC46") (pin "21") (pinfunction "UART_RX/SPI_MOSI_21") (pintype "passive"))
    )
    (net (code "22") (name "/GNSS_UART_TX") (class "Default")
      (node (ref "IC46") (pin "20") (pinfunction "UART_TX/SPI_MISO_20") (pintype "passive"))
    )
    (net (code "23") (name "/GNSS_USB_VDD") (class "Default")
      (node (ref "IC46") (pin "7") (pinfunction "VDD_USB_7") (pintype "passive"))
      (node (ref "R245") (pin "1") (pinfunction "1_1") (pintype "passive"))
      (node (ref "R246") (pin "1") (pinfunction "1_1") (pintype "passive"))
    )
    (net (code "24") (name "/GNSS_VCC_RF") (class "Default")
      (node (ref "IC46") (pin "9") (pinfunction "VCC_RF_9") (pintype "passive"))
      (node (ref "R242") (pin "2") (pinfunction "2_2") (pintype "passive"))
    )
    (net (code "25") (name "/LM75_OS") (class "Default")
      (node (ref "IC42") (pin "3") (pinfunction "OS_3") (pintype "passive"))
      (node (ref "R206") (pin "1") (pinfunction "1_1") (pintype "passive"))
      (node (ref "R235") (pin "1") (pinfunction "1_1") (pintype "passive"))
    )
    (net (code "26") (name "/PMOD_A_PIN1") (class "Default")
      (node (ref "R200") (pin "1") (pinfunction "1_1") (pintype "passive"))
    )
    (net (code "27") (name "/PMOD_A_PIN2") (class "Default")
      (node (ref "R208") (pin "1") (pinfunction "1_1") (pintype "passive"))
    )
    (net (code "28") (name "/PMOD_A_PIN3") (class "Default")
      (node (ref "R210") (pin "1") (pinfunction "1_1") (pintype "passive"))
    )
    (net (code "29") (name "/PMOD_A_PIN4") (class "Default")
      (node (ref "R214") (pin "1") (pinfunction "1_1") (pintype "passive"))
    )
    (net (code "30") (name "/PMOD_A_PIN7") (class "Default")
      (node (ref "R201") (pin "2") (pinfunction "2_2") (pintype "passive"))
    )
    (net (code "31") (name "/PMOD_A_PIN8") (class "Default")
      (node (ref "R209") (pin "2") (pinfunction "2_2") (pintype "passive"))
    )
    (net (code "32") (name "/PMOD_A_PIN9") (class "Default")
      (node (ref "R211") (pin "2") (pinfunction "2_2") (pintype "passive"))
    )
    (net (code "33") (name "/PMOD_A_PIN10") (class "Default")
      (node (ref "R215") (pin "2") (pinfunction "2_2") (pintype "passive"))
    )
    (net (code "34") (name "/PMOD_B_PIN1") (class "Default")
      (node (ref "R227") (pin "1") (pinfunction "1_1") (pintype "passive"))
    )
    (net (code "35") (name "/PMOD_B_PIN2") (class "Default")
      (node (ref "R230") (pin "1") (pinfunction "1_1") (pintype "passive"))
    )
    (net (code "36") (name "/PMOD_B_PIN3") (class "Default")
      (node (ref "R233") (pin "1") (pinfunction "1_1") (pintype "passive"))
    )
    (net (code "37") (name "/PMOD_B_PIN4") (class "Default")
      (node (ref "R237") (pin "1") (pinfunction "1_1") (pintype "passive"))
    )
    (net (code "38") (name "/PMOD_B_PIN7") (class "Default")
      (node (ref "R228") (pin "2") (pinfunction "2_2") (pintype "passive"))
    )
    (net (code "39") (name "/PMOD_B_PIN8") (class "Default")
      (node (ref "R231") (pin "2") (pinfunction "2_2") (pintype "passive"))
    )
    (net (code "40") (name "/PMOD_B_PIN9") (class "Default")
      (node (ref "R234") (pin "2") (pinfunction "2_2") (pintype "passive"))
    )
    (net (code "41") (name "/PMOD_B_PIN10") (class "Default")
      (node (ref "R238") (pin "2") (pinfunction "2_2") (pintype "passive"))
    )
    (net (code "42") (name "GND") (class "Default")
      (node (ref "C502") (pin "2") (pinfunction "2_2") (pintype "passive"))
      (node (ref "C503") (pin "2") (pinfunction "2_2") (pintype "passive"))
      (node (ref "C507") (pin "2") (pinfunction "2_2") (pintype "passive"))
      (node (ref "C508") (pin "2") (pinfunction "2_2") (pintype "passive"))
      (node (ref "C509") (pin "2") (pinfunction "2_2") (pintype "passive"))
      (node (ref "C510") (pin "2") (pinfunction "2_2") (pintype "passive"))
      (node (ref "C511") (pin "1") (pinfunction "1_1") (pintype "passive"))
      (node (ref "C512") (pin "1") (pinfunction "1_1") (pintype "passive"))
      (node (ref "C513") (pin "1") (pinfunction "1_1") (pintype "passive"))
      (node (ref "C515") (pin "1") (pinfunction "1_1") (pintype "passive"))
      (node (ref "C516") (pin "2") (pinfunction "2_2") (pintype "passive"))
      (node (ref "C517") (pin "2") (pinfunction "2_2") (pintype "passive"))
      (node (ref "C518") (pin "1") (pinfunction "1_1") (pintype "passive"))
      (node (ref "C519") (pin "2") (pinfunction "2_2") (pintype "passive"))
      (node (ref "ESD14") (pin "2") (pinfunction "2_2") (pintype "passive"))
      (node (ref "IC42") (pin "4") (pinfunction "GND_4") (pintype "passive"))
      (node (ref "IC42") (pin "5") (pinfunction "A2_5") (pintype "passive"))
      (node (ref "IC42") (pin "6") (pinfunction "A1_6") (pintype "passive"))
      (node (ref "IC42") (pin "7") (pinfunction "A0_7") (pintype "passive"))
      (node (ref "IC43") (pin "1") (pinfunction "A0_1") (pintype "passive"))
      (node (ref "IC43") (pin "2") (pinfunction "A1_2") (pintype "passive"))
      (node (ref "IC43") (pin "3") (pinfunction "A2_3") (pintype "passive"))
      (node (ref "IC43") (pin "4") (pinfunction "VSS_4") (pintype "passive"))
      (node (ref "IC43") (pin "7") (pinfunction "WP_7") (pintype "passive"))
      (node (ref "IC44") (pin "4") (pinfunction "GND_4") (pintype "passive"))
      (node (ref "IC45") (pin "4") (pinfunction "GND_4") (pintype "passive"))
      (node (ref "IC46") (pin "10") (pinfunction "GND_10") (pintype "passive"))
      (node (ref "IC46") (pin "12") (pinfunction "GND_12") (pintype "passive"))
      (node (ref "IC46") (pin "13") (pinfunction "GND_13") (pintype "passive"))
      (node (ref "IC46") (pin "24") (pinfunction "GND_24") (pintype "passive"))
      (node (ref "IC47") (pin "2") (pinfunction "GND_2") (pintype "passive"))
      (node (ref "IC47") (pin "5") (pinfunction "DIR_5") (pintype "input"))
      (node (ref "J15") (pin "11") (pinfunction "11_11") (pintype "passive"))
      (node (ref "J15") (pin "5") (pinfunction "5_5") (pintype "passive"))
      (node (ref "J19") (pin "11") (pinfunction "11_11") (pintype "passive"))
      (node (ref "J19") (pin "5") (pinfunction "5_5") (pintype "passive"))
      (node (ref "J20") (pin "1") (pinfunction "1_1") (pintype "passive"))
      (node (ref "J21") (pin "2") (pinfunction "Y_2") (pintype "passive"))
      (node (ref "J22") (pin "2") (pinfunction "Y_2") (pintype "passive"))
      (node (ref "J23") (pin "2") (pinfunction "Y_2") (pintype "passive"))
      (node (ref "LED5") (pin "1") (pinfunction "C1_1") (pintype "power_in"))
      (node (ref "R232") (pin "1") (pinfunction "1_1") (pintype "passive"))
      (node (ref "R236") (pin "2") (pinfunction "2_2") (pintype "passive"))
      (node (ref "R246") (pin "2") (pinfunction "2_2") (pintype "passive"))
      (node (ref "R247") (pin "1") (pinfunction "1_1") (pintype "passive"))
      (node (ref "R249") (pin "1") (pinfunction "1_1") (pintype "passive"))
      (node (ref "R252") (pin "1") (pinfunction "1_1") (pintype "passive"))
      (node (ref "SW1") (pin "1") (pinfunction "A1_1") (pintype "passive"))
      (node (ref "SW1") (pin "3") (pinfunction "A2_3") (pintype "passive"))
      (node (ref "SW1") (pin "5") (pinfunction "A3_5") (pintype "passive"))
      (node (ref "SW1") (pin "7") (pinfunction "A4_7") (pintype "passive"))
      (node (ref "VT2") (pin "S") (pinfunction "S_S") (pintype "passive"))
    )
    (net (code "43") (name "Net-(C503-Pad1)") (class "Default")
      (node (ref "C503") (pin "1") (pinfunction "1_1") (pintype "passive"))
      (node (ref "J15") (pin "12") (pinfunction "12_12") (pintype "passive"))
      (node (ref "J15") (pin "6") (pinfunction "6_6") (pintype "passive"))
      (node (ref "R218") (pin "1") (pinfunction "1_1") (pintype "passive"))
      (node (ref "R219") (pin "2") (pinfunction "2_2") (pintype "passive"))
    )
    (net (code "44") (name "Net-(C504-Pad1)") (class "Default")
      (node (ref "C504") (pin "1") (pinfunction "1_1") (pintype "passive"))
      (node (ref "C505") (pin "1") (pinfunction "1_1") (pintype "passive"))
      (node (ref "C506") (pin "1") (pinfunction "1_1") (pintype "passive"))
      (node (ref "C507") (pin "1") (pinfunction "1_1") (pintype "passive"))
      (node (ref "J16") (pin "2") (pinfunction "2_2") (pintype "passive"))
      (node (ref "J17") (pin "2") (pinfunction "2_2") (pintype "passive"))
      (node (ref "J18") (pin "2") (pinfunction "2_2") (pintype "passive"))
      (node (ref "R223") (pin "1") (pinfunction "1_1") (pintype "passive"))
      (node (ref "R224") (pin "1") (pinfunction "1_1") (pintype "passive"))
      (node (ref "R225") (pin "1") (pinfunction "1_1") (pintype "passive"))
    )
    (net (code "45") (name "Net-(C504-Pad2)") (class "Default")
      (node (ref "C504") (pin "2") (pinfunction "2_2") (pintype "passive"))
      (node (ref "C505") (pin "2") (pinfunction "2_2") (pintype "passive"))
      (node (ref "C506") (pin "2") (pinfunction "2_2") (pintype "passive"))
      (node (ref "J16") (pin "1") (pinfunction "1_1") (pintype "passive"))
      (node (ref "J17") (pin "1") (pinfunction "1_1") (pintype "passive"))
      (node (ref "J18") (pin "1") (pinfunction "1_1") (pintype "passive"))
      (node (ref "R232") (pin "2") (pinfunction "2_2") (pintype "passive"))
      (node (ref "VT2") (pin "D") (pinfunction "D_D") (pintype "passive"))
    )
    (net (code "46") (name "Net-(C509-Pad1)") (class "Default")
      (node (ref "C509") (pin "1") (pinfunction "1_1") (pintype "passive"))
      (node (ref "J19") (pin "12") (pinfunction "12_12") (pintype "passive"))
      (node (ref "J19") (pin "6") (pinfunction "6_6") (pintype "passive"))
      (node (ref "R240") (pin "1") (pinfunction "1_1") (pintype "passive"))
      (node (ref "R241") (pin "2") (pinfunction "2_2") (pintype "passive"))
    )
    (net (code "47") (name "Net-(C511-Pad2)") (class "Default")
      (node (ref "C511") (pin "2") (pinfunction "2_2") (pintype "passive"))
      (node (ref "L9") (pin "2") (pinfunction "2_2") (pintype "passive"))
      (node (ref "R244") (pin "2") (pinfunction "2_2") (pintype "passive"))
    )
    (net (code "48") (name "Net-(IC46-D_SEL)") (class "Default")
      (node (ref "IC46") (pin "2") (pinfunction "D_SEL_2") (pintype "passive"))
      (node (ref "R249") (pin "2") (pinfunction "2_2") (pintype "passive"))
    )
    (net (code "49") (name "Net-(IC46-RF_IN)") (class "Default")
      (node (ref "C514") (pin "2") (pinfunction "2_2") (pintype "passive"))
      (node (ref "IC46") (pin "11") (pinfunction "RF_IN_11") (pintype "passive"))
    )
    (net (code "50") (name "Net-(IC46-SAFEBOOT_N)") (class "Default")
      (node (ref "IC46") (pin "1") (pinfunction "SAFEBOOT_N_1") (pintype "passive"))
      (node (ref "R252") (pin "2") (pinfunction "2_2") (pintype "passive"))
    )
    (net (code "51") (name "Net-(IC46-V_BCKP)") (class "Default")
      (node (ref "C517") (pin "1") (pinfunction "1_1") (pintype "passive"))
      (node (ref "IC46") (pin "22") (pinfunction "V_BCKP_22") (pintype "passive"))
      (node (ref "R250") (pin "1") (pinfunction "1_1") (pintype "passive"))
      (node (ref "R251") (pin "1") (pinfunction "1_1") (pintype "passive"))
    )
    (net (code "52") (name "Net-(J15-Pad1)") (class "Default")
      (node (ref "J15") (pin "1") (pinfunction "1_1") (pintype "passive"))
      (node (ref "R200") (pin "2") (pinfunction "2_2") (pintype "passive"))
    )
    (net (code "53") (name "Net-(J15-Pad2)") (class "Default")
      (node (ref "J15") (pin "2") (pinfunction "2_2") (pintype "passive"))
      (node (ref "R208") (pin "2") (pinfunction "2_2") (pintype "passive"))
    )
    (net (code "54") (name "Net-(J15-Pad3)") (class "Default")
      (node (ref "J15") (pin "3") (pinfunction "3_3") (pintype "passive"))
      (node (ref "R210") (pin "2") (pinfunction "2_2") (pintype "passive"))
    )
    (net (code "55") (name "Net-(J15-Pad4)") (class "Default")
      (node (ref "J15") (pin "4") (pinfunction "4_4") (pintype "passive"))
      (node (ref "R214") (pin "2") (pinfunction "2_2") (pintype "passive"))
    )
    (net (code "56") (name "Net-(J15-Pad7)") (class "Default")
      (node (ref "J15") (pin "7") (pinfunction "7_7") (pintype "passive"))
      (node (ref "R201") (pin "1") (pinfunction "1_1") (pintype "passive"))
    )
    (net (code "57") (name "Net-(J15-Pad8)") (class "Default")
      (node (ref "J15") (pin "8") (pinfunction "8_8") (pintype "passive"))
      (node (ref "R209") (pin "1") (pinfunction "1_1") (pintype "passive"))
    )
    (net (code "58") (name "Net-(J15-Pad9)") (class "Default")
      (node (ref "J15") (pin "9") (pinfunction "9_9") (pintype "passive"))
      (node (ref "R211") (pin "1") (pinfunction "1_1") (pintype "passive"))
    )
    (net (code "59") (name "Net-(J15-Pad10)") (class "Default")
      (node (ref "J15") (pin "10") (pinfunction "10_10") (pintype "passive"))
      (node (ref "R215") (pin "1") (pinfunction "1_1") (pintype "passive"))
    )
    (net (code "60") (name "Net-(J19-Pad1)") (class "Default")
      (node (ref "J19") (pin "1") (pinfunction "1_1") (pintype "passive"))
      (node (ref "R227") (pin "2") (pinfunction "2_2") (pintype "passive"))
    )
    (net (code "61") (name "Net-(J19-Pad2)") (class "Default")
      (node (ref "J19") (pin "2") (pinfunction "2_2") (pintype "passive"))
      (node (ref "R230") (pin "2") (pinfunction "2_2") (pintype "passive"))
    )
    (net (code "62") (name "Net-(J19-Pad3)") (class "Default")
      (node (ref "J19") (pin "3") (pinfunction "3_3") (pintype "passive"))
      (node (ref "R233") (pin "2") (pinfunction "2_2") (pintype "passive"))
    )
    (net (code "63") (name "Net-(J19-Pad4)") (class "Default")
      (node (ref "J19") (pin "4") (pinfunction "4_4") (pintype "passive"))
      (node (ref "R237") (pin "2") (pinfunction "2_2") (pintype "passive"))
    )
    (net (code "64") (name "Net-(J19-Pad7)") (class "Default")
      (node (ref "J19") (pin "7") (pinfunction "7_7") (pintype "passive"))
      (node (ref "R228") (pin "1") (pinfunction "1_1") (pintype "passive"))
    )
    (net (code "65") (name "Net-(J19-Pad8)") (class "Default")
      (node (ref "J19") (pin "8") (pinfunction "8_8") (pintype "passive"))
      (node (ref "R231") (pin "1") (pinfunction "1_1") (pintype "passive"))
    )
    (net (code "66") (name "Net-(J19-Pad9)") (class "Default")
      (node (ref "J19") (pin "9") (pinfunction "9_9") (pintype "passive"))
      (node (ref "R234") (pin "1") (pinfunction "1_1") (pintype "passive"))
    )
    (net (code "67") (name "Net-(J19-Pad10)") (class "Default")
      (node (ref "J19") (pin "10") (pinfunction "10_10") (pintype "passive"))
      (node (ref "R238") (pin "1") (pinfunction "1_1") (pintype "passive"))
    )
    (net (code "68") (name "Net-(LED1-C1)") (class "Default")
      (node (ref "LED1") (pin "1") (pinfunction "C1_1") (pintype "power_in"))
      (node (ref "R207") (pin "1") (pinfunction "1_1") (pintype "passive"))
    )
    (net (code "69") (name "Net-(LED1-C2)") (class "Default")
      (node (ref "LED1") (pin "2") (pinfunction "C2_2") (pintype "power_in"))
      (node (ref "R212") (pin "1") (pinfunction "1_1") (pintype "passive"))
    )
    (net (code "70") (name "Net-(LED2-C1)") (class "Default")
      (node (ref "LED2") (pin "1") (pinfunction "C1_1") (pintype "power_in"))
      (node (ref "R217") (pin "1") (pinfunction "1_1") (pintype "passive"))
    )
    (net (code "71") (name "Net-(LED2-C2)") (class "Default")
      (node (ref "LED2") (pin "2") (pinfunction "C2_2") (pintype "power_in"))
      (node (ref "R220") (pin "1") (pinfunction "1_1") (pintype "passive"))
    )
    (net (code "72") (name "Net-(LED3-C1)") (class "Default")
      (node (ref "LED3") (pin "1") (pinfunction "C1_1") (pintype "power_in"))
      (node (ref "R221") (pin "1") (pinfunction "1_1") (pintype "passive"))
    )
    (net (code "73") (name "Net-(LED3-C2)") (class "Default")
      (node (ref "LED3") (pin "2") (pinfunction "C2_2") (pintype "power_in"))
      (node (ref "R222") (pin "1") (pinfunction "1_1") (pintype "passive"))
    )
    (net (code "74") (name "Net-(LED4-C1)") (class "Default")
      (node (ref "LED4") (pin "1") (pinfunction "C1_1") (pintype "power_in"))
      (node (ref "R226") (pin "1") (pinfunction "1_1") (pintype "passive"))
    )
    (net (code "75") (name "Net-(LED4-C2)") (class "Default")
      (node (ref "LED4") (pin "2") (pinfunction "C2_2") (pintype "power_in"))
      (node (ref "R229") (pin "1") (pinfunction "1_1") (pintype "passive"))
    )
    (net (code "76") (name "Net-(LED5-A)") (class "Default")
      (node (ref "LED5") (pin "3") (pinfunction "A_3") (pintype "power_in"))
      (node (ref "R239") (pin "2") (pinfunction "2_2") (pintype "passive"))
    )
    (net (code "77") (name "Net-(R242-Pad1)") (class "Default")
      (node (ref "R242") (pin "1") (pinfunction "1_1") (pintype "passive"))
      (node (ref "R243") (pin "2") (pinfunction "2_2") (pintype "passive"))
      (node (ref "R244") (pin "1") (pinfunction "1_1") (pintype "passive"))
    )
    (net (code "78") (name "VCC1P8A") (class "Default")
      (node (ref "C516") (pin "1") (pinfunction "1_1") (pintype "passive"))
      (node (ref "IC47") (pin "6") (pinfunction "VCCB_6") (pintype "power_in"))
    )
    (net (code "79") (name "VCC2P5") (class "Default")
      (node (ref "C515") (pin "2") (pinfunction "2_2") (pintype "passive"))
      (node (ref "IC47") (pin "1") (pinfunction "VCCA_1") (pintype "power_in"))
      (node (ref "R202") (pin "1") (pinfunction "1_1") (pintype "passive"))
      (node (ref "R203") (pin "1") (pinfunction "1_1") (pintype "passive"))
      (node (ref "R204") (pin "1") (pinfunction "1_1") (pintype "passive"))
      (node (ref "R205") (pin "1") (pinfunction "1_1") (pintype "passive"))
      (node (ref "R206") (pin "2") (pinfunction "2_2") (pintype "passive"))
    )
    (net (code "80") (name "VCC3P0_BATT") (class "Default")
      (node (ref "J20") (pin "2") (pinfunction "2_2") (pintype "passive"))
      (node (ref "R250") (pin "2") (pinfunction "2_2") (pintype "passive"))
    )
    (net (code "81") (name "VCC3P3") (class "Default")
      (node (ref "C502") (pin "1") (pinfunction "1_1") (pintype "passive"))
      (node (ref "C508") (pin "1") (pinfunction "1_1") (pintype "passive"))
      (node (ref "C510") (pin "1") (pinfunction "1_1") (pintype "passive"))
      (node (ref "IC42") (pin "8") (pinfunction "VCC_8") (pintype "passive"))
      (node (ref "IC43") (pin "8") (pinfunction "VCC_8") (pintype "passive"))
      (node (ref "IC44") (pin "8") (pinfunction "VCC_8") (pintype "power_in"))
      (node (ref "IC45") (pin "8") (pinfunction "VCC_8") (pintype "power_in"))
      (node (ref "LED1") (pin "3") (pinfunction "A_3") (pintype "power_in"))
      (node (ref "LED2") (pin "3") (pinfunction "A_3") (pintype "power_in"))
      (node (ref "LED3") (pin "3") (pinfunction "A_3") (pintype "power_in"))
      (node (ref "LED4") (pin "3") (pinfunction "A_3") (pintype "power_in"))
      (node (ref "R213") (pin "1") (pinfunction "1_1") (pintype "passive"))
      (node (ref "R216") (pin "1") (pinfunction "1_1") (pintype "passive"))
      (node (ref "R218") (pin "2") (pinfunction "2_2") (pintype "passive"))
      (node (ref "R223") (pin "2") (pinfunction "2_2") (pintype "passive"))
      (node (ref "R239") (pin "1") (pinfunction "1_1") (pintype "passive"))
      (node (ref "R240") (pin "2") (pinfunction "2_2") (pintype "passive"))
    )
    (net (code "82") (name "VCC3P3_CLK") (class "Default")
      (node (ref "FR104") (pin "1") (pinfunction "1_1") (pintype "passive"))
    )
    (net (code "83") (name "VCC3P3_GNSS") (class "Default")
      (node (ref "C512") (pin "2") (pinfunction "2_2") (pintype "passive"))
      (node (ref "C513") (pin "2") (pinfunction "2_2") (pintype "passive"))
      (node (ref "C518") (pin "2") (pinfunction "2_2") (pintype "passive"))
      (node (ref "C519") (pin "1") (pinfunction "1_1") (pintype "passive"))
      (node (ref "FR104") (pin "2") (pinfunction "2_2") (pintype "passive"))
      (node (ref "IC46") (pin "23") (pinfunction "VCC_23") (pintype "passive"))
      (node (ref "R243") (pin "1") (pinfunction "1_1") (pintype "passive"))
      (node (ref "R245") (pin "2") (pinfunction "2_2") (pintype "passive"))
      (node (ref "R251") (pin "2") (pinfunction "2_2") (pintype "passive"))
    )
    (net (code "84") (name "VCC5P0") (class "Default")
      (node (ref "R219") (pin "1") (pinfunction "1_1") (pintype "passive"))
      (node (ref "R224") (pin "2") (pinfunction "2_2") (pintype "passive"))
      (node (ref "R241") (pin "1") (pinfunction "1_1") (pintype "passive"))
    )
    (net (code "85") (name "VCC12P0") (class "Default")
      (node (ref "R225") (pin "2") (pinfunction "2_2") (pintype "passive"))
    )
    (net (code "86") (name "unconnected-(IC44-NC-Pad1)") (class "Default")
      (node (ref "IC44") (pin "1") (pinfunction "NC_1") (pintype "passive+no_connect"))
    )
    (net (code "87") (name "unconnected-(IC44-NC-Pad2)") (class "Default")
      (node (ref "IC44") (pin "2") (pinfunction "NC_2") (pintype "passive+no_connect"))
    )
    (net (code "88") (name "unconnected-(IC44-NC-Pad3)") (class "Default")
      (node (ref "IC44") (pin "3") (pinfunction "NC_3") (pintype "passive+no_connect"))
    )
    (net (code "89") (name "unconnected-(IC44-NC-Pad7)") (class "Default")
      (node (ref "IC44") (pin "7") (pinfunction "NC_7") (pintype "passive+no_connect"))
    )
    (net (code "90") (name "unconnected-(IC45-NC-Pad1)") (class "Default")
      (node (ref "IC45") (pin "1") (pinfunction "NC_1") (pintype "passive+no_connect"))
    )
    (net (code "91") (name "unconnected-(IC45-NC-Pad2)") (class "Default")
      (node (ref "IC45") (pin "2") (pinfunction "NC_2") (pintype "passive+no_connect"))
    )
    (net (code "92") (name "unconnected-(IC45-NC-Pad3)") (class "Default")
      (node (ref "IC45") (pin "3") (pinfunction "NC_3") (pintype "passive+no_connect"))
    )
    (net (code "93") (name "unconnected-(IC45-NC-Pad7)") (class "Default")
      (node (ref "IC45") (pin "7") (pinfunction "NC_7") (pintype "passive+no_connect"))
    )
    (net (code "94") (name "unconnected-(IC46-DDC_SCL{slash}SPI_CLK-Pad19)") (class "Default")
      (node (ref "IC46") (pin "19") (pinfunction "DDC_SCL/SPI_CLK_19") (pintype "passive+no_connect"))
    )
    (net (code "95") (name "unconnected-(IC46-DDC_SDA{slash}SPI_CSN-Pad18)") (class "Default")
      (node (ref "IC46") (pin "18") (pinfunction "DDC_SDA/SPI_CSN_18") (pintype "passive+no_connect"))
    )
    (net (code "96") (name "unconnected-(IC46-EXTINT-Pad4)") (class "Default")
      (node (ref "IC46") (pin "4") (pinfunction "EXTINT_4") (pintype "passive+no_connect"))
    )
    (net (code "97") (name "unconnected-(IC46-GEOFENCE_STAT{slash}RESV-Pad16)") (class "Default")
      (node (ref "IC46") (pin "16") (pinfunction "GEOFENCE_STAT/RESV_16") (pintype "passive+no_connect"))
    )
    (net (code "98") (name "unconnected-(IC46-LNA_EN{slash}RESV-Pad14)") (class "Default")
      (node (ref "IC46") (pin "14") (pinfunction "LNA_EN/RESV_14") (pintype "passive+no_connect"))
    )
    (net (code "99") (name "unconnected-(IC46-RESET_N-Pad8)") (class "Default")
      (node (ref "IC46") (pin "8") (pinfunction "RESET_N_8") (pintype "passive+no_connect"))
    )
    (net (code "100") (name "unconnected-(IC46-RESV-Pad17)") (class "Default")
      (node (ref "IC46") (pin "17") (pinfunction "RESV_17") (pintype "passive+no_connect"))
    )
    (net (code "101") (name "unconnected-(IC46-RTK_STAT{slash}RESV-Pad15)") (class "Default")
      (node (ref "IC46") (pin "15") (pinfunction "RTK_STAT/RESV_15") (pintype "passive+no_connect"))
    )
    (net (code "102") (name "unconnected-(IC46-USB_DM-Pad5)") (class "Default")
      (node (ref "IC46") (pin "5") (pinfunction "USB_DM_5") (pintype "passive+no_connect"))
    )
    (net (code "103") (name "unconnected-(IC46-USB_DP-Pad6)") (class "Default")
      (node (ref "IC46") (pin "6") (pinfunction "USB_DP_6") (pintype "passive+no_connect"))
    )
    (net (code "104") (name "unconnected-(LED5-C2-Pad2)") (class "Default")
      (node (ref "LED5") (pin "2") (pinfunction "C2_2") (pintype "power_in+no_connect"))
    )
  )
)
